# pc_sensything_v1_2.net
KiCad netlist of a schematic drawn in EAGLE
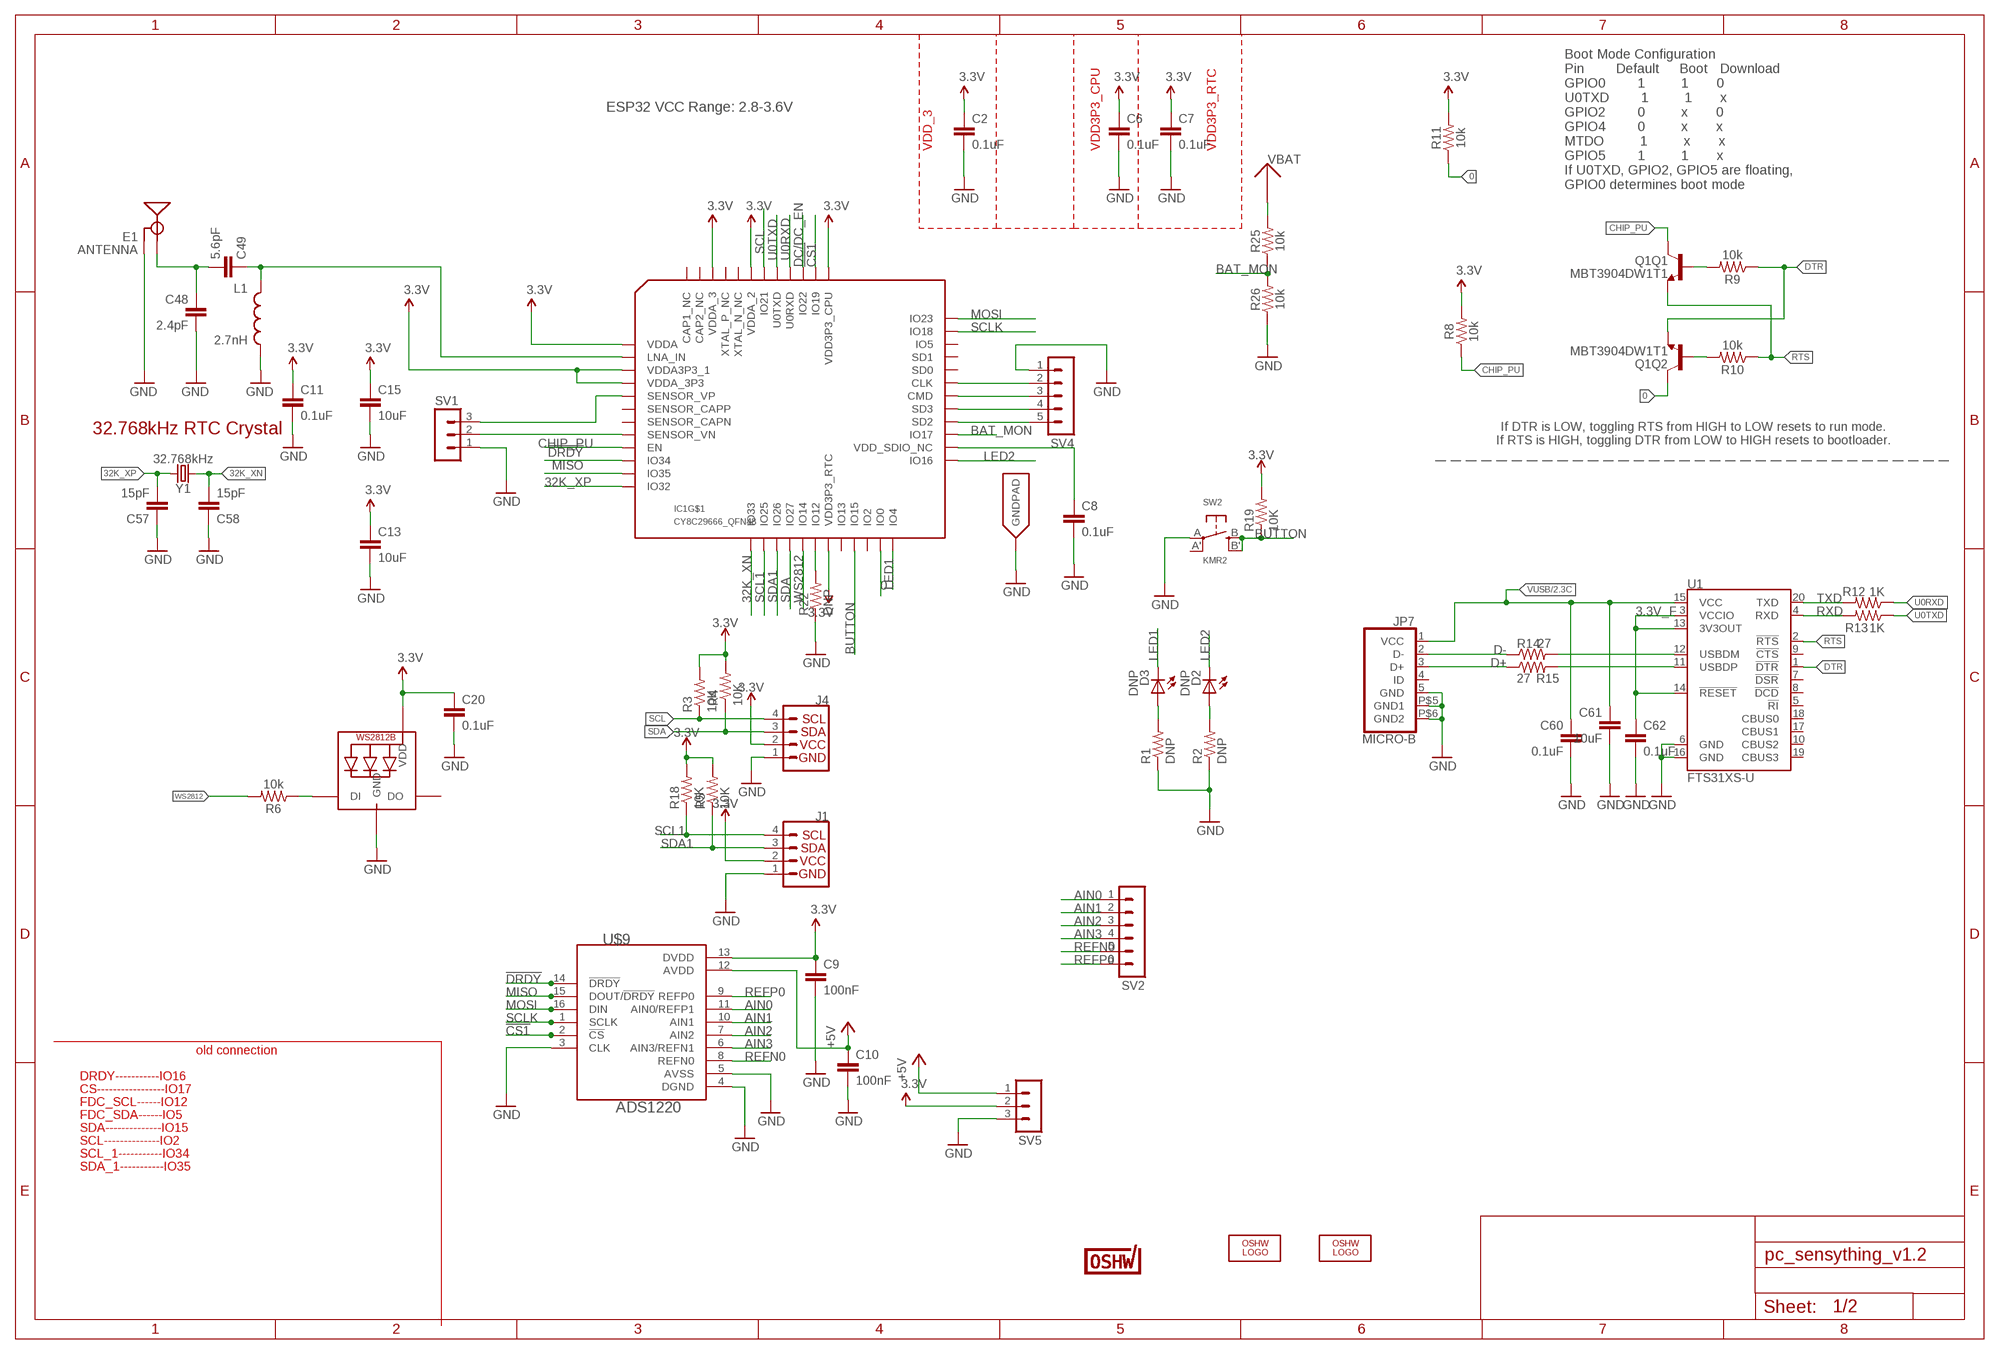
[diagram p0: schematic, sheet 1]
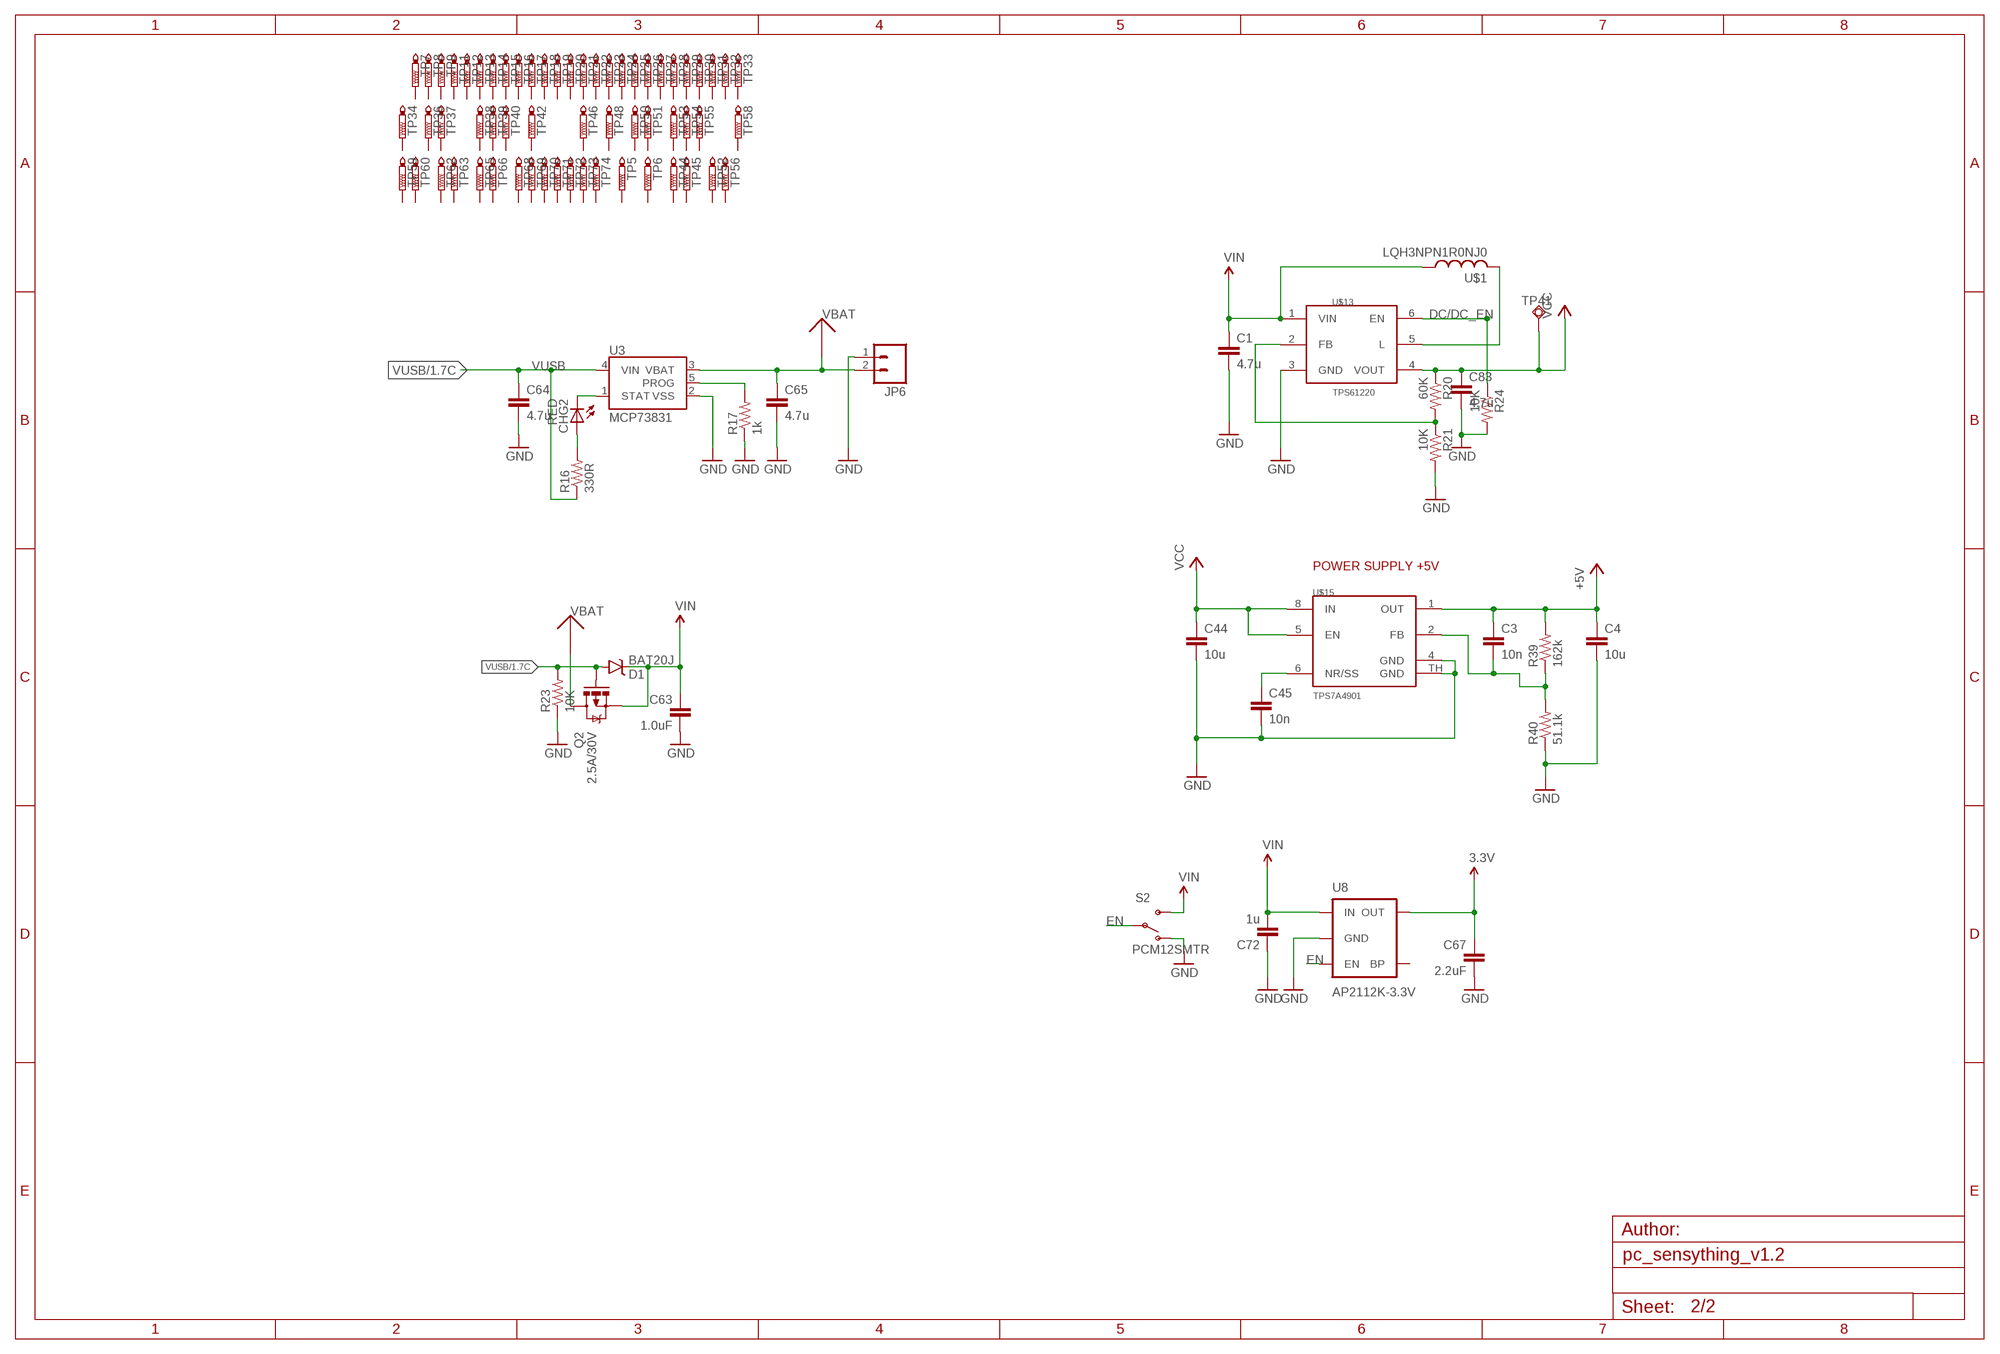
[diagram p1: schematic, sheet 2]

(export (version "E")
  (design (tool "Eeschema 10.0.6"))
  (components
    (comp (ref "C1")
      (value "4.7u")
      (footprint "eagle-import:C0805")
      (libsource (lib "eagle-import") (part "C-EUC0805"))
    )
    (comp (ref "C3")
      (value "10n")
      (footprint "eagle-import:C0402")
      (libsource (lib "eagle-import") (part "C-EUC0402"))
    )
    (comp (ref "C4")
      (value "10u")
      (footprint "eagle-import:C0805")
      (libsource (lib "eagle-import") (part "C-EUC0805"))
    )
    (comp (ref "C44")
      (value "10u")
      (footprint "eagle-import:C0805")
      (libsource (lib "eagle-import") (part "C-EUC0805"))
    )
    (comp (ref "C45")
      (value "10n")
      (footprint "eagle-import:C0402")
      (libsource (lib "eagle-import") (part "C-EUC0402"))
    )
    (comp (ref "C63")
      (value "1.0uF")
      (footprint "eagle-import:C0402")
      (libsource (lib "eagle-import") (part "C-EUC0402"))
    )
    (comp (ref "C64")
      (value "4.7u")
      (footprint "eagle-import:C0805")
      (libsource (lib "eagle-import") (part "C-EUC0805"))
    )
    (comp (ref "C65")
      (value "4.7u")
      (footprint "eagle-import:C0805")
      (libsource (lib "eagle-import") (part "C-EUC0805"))
    )
    (comp (ref "C67")
      (value "2.2uF")
      (footprint "eagle-import:C0402")
      (libsource (lib "eagle-import") (part "C-EUC0402"))
    )
    (comp (ref "C72")
      (value "1u")
      (footprint "eagle-import:C0402")
      (libsource (lib "eagle-import") (part "C-EUC0402"))
    )
    (comp (ref "C83")
      (value "4.7u")
      (footprint "eagle-import:C0805")
      (libsource (lib "eagle-import") (part "C-EUC0805"))
    )
    (comp (ref "CHG2")
      (value "RED")
      (footprint "eagle-import:CHIPLED_0603")
      (libsource (lib "eagle-import") (part "LEDCHIPLED_0603"))
    )
    (comp (ref "D1")
      (value "BAT20J")
      (footprint "eagle-import:SOD-323")
      (libsource (lib "eagle-import") (part "DIODE-SCHOTTKY-BAT20J"))
    )
    (comp (ref "JP6")
      (value "M02-JST-2MM-SMT")
      (footprint "eagle-import:JST-2-SMD")
      (libsource (lib "eagle-import") (part "M02-JST-2MM-SMT"))
    )
    (comp (ref "Q2")
      (value "2.5A/30V")
      (footprint "eagle-import:SOT23-3")
      (libsource (lib "eagle-import") (part "MOSFET-PCHANNELDMG2307L"))
    )
    (comp (ref "R16")
      (value "330R")
      (footprint "eagle-import:R0402")
      (libsource (lib "eagle-import") (part "R-US_R0402"))
    )
    (comp (ref "R17")
      (value "1k")
      (footprint "eagle-import:R0402")
      (libsource (lib "eagle-import") (part "R-US_R0402"))
    )
    (comp (ref "R20")
      (value "60K")
      (footprint "eagle-import:R0805")
      (libsource (lib "eagle-import") (part "R-US_R0805"))
    )
    (comp (ref "R21")
      (value "10K")
      (footprint "eagle-import:R0805")
      (libsource (lib "eagle-import") (part "R-US_R0805"))
    )
    (comp (ref "R23")
      (value "10K")
      (footprint "eagle-import:R0402")
      (libsource (lib "eagle-import") (part "R-US_R0402"))
    )
    (comp (ref "R24")
      (value "10K")
      (footprint "eagle-import:R0402")
      (libsource (lib "eagle-import") (part "R-US_R0402"))
    )
    (comp (ref "R39")
      (value "162k")
      (footprint "eagle-import:R0805")
      (libsource (lib "eagle-import") (part "R-US_R0805"))
    )
    (comp (ref "R40")
      (value "51.1k")
      (footprint "eagle-import:R0805")
      (libsource (lib "eagle-import") (part "R-US_R0805"))
    )
    (comp (ref "S2")
      (value "PCM12SMTR")
      (footprint "eagle-import:SWITCH-SPST-SMD-A")
      (libsource (lib "eagle-import") (part "SWITCH-SPDT-SMD-A"))
    )
    (comp (ref "TP5")
      (value "PTR1PAD1-13")
      (footprint "eagle-import:P1-13")
      (libsource (lib "eagle-import") (part "PTR1PAD1-13"))
    )
    (comp (ref "TP6")
      (value "PTR1PAD1-13")
      (footprint "eagle-import:P1-13")
      (libsource (lib "eagle-import") (part "PTR1PAD1-13"))
    )
    (comp (ref "TP7")
      (value "PTR1PAD1-13")
      (footprint "eagle-import:P1-13")
      (libsource (lib "eagle-import") (part "PTR1PAD1-13"))
    )
    (comp (ref "TP8")
      (value "PTR1PAD1-13")
      (footprint "eagle-import:P1-13")
      (libsource (lib "eagle-import") (part "PTR1PAD1-13"))
    )
    (comp (ref "TP9")
      (value "PTR1PAD1-13")
      (footprint "eagle-import:P1-13")
      (libsource (lib "eagle-import") (part "PTR1PAD1-13"))
    )
    (comp (ref "TP11")
      (value "PTR1PAD1-13")
      (footprint "eagle-import:P1-13")
      (libsource (lib "eagle-import") (part "PTR1PAD1-13"))
    )
    (comp (ref "TP12")
      (value "PTR1PAD1-13")
      (footprint "eagle-import:P1-13")
      (libsource (lib "eagle-import") (part "PTR1PAD1-13"))
    )
    (comp (ref "TP13")
      (value "PTR1PAD1-13")
      (footprint "eagle-import:P1-13")
      (libsource (lib "eagle-import") (part "PTR1PAD1-13"))
    )
    (comp (ref "TP14")
      (value "PTR1PAD1-13")
      (footprint "eagle-import:P1-13")
      (libsource (lib "eagle-import") (part "PTR1PAD1-13"))
    )
    (comp (ref "TP15")
      (value "PTR1PAD1-13")
      (footprint "eagle-import:P1-13")
      (libsource (lib "eagle-import") (part "PTR1PAD1-13"))
    )
    (comp (ref "TP16")
      (value "PTR1PAD1-13")
      (footprint "eagle-import:P1-13")
      (libsource (lib "eagle-import") (part "PTR1PAD1-13"))
    )
    (comp (ref "TP17")
      (value "PTR1PAD1-13")
      (footprint "eagle-import:P1-13")
      (libsource (lib "eagle-import") (part "PTR1PAD1-13"))
    )
    (comp (ref "TP18")
      (value "PTR1PAD1-13")
      (footprint "eagle-import:P1-13")
      (libsource (lib "eagle-import") (part "PTR1PAD1-13"))
    )
    (comp (ref "TP19")
      (value "PTR1PAD1-13")
      (footprint "eagle-import:P1-13")
      (libsource (lib "eagle-import") (part "PTR1PAD1-13"))
    )
    (comp (ref "TP20")
      (value "PTR1PAD1-13")
      (footprint "eagle-import:P1-13")
      (libsource (lib "eagle-import") (part "PTR1PAD1-13"))
    )
    (comp (ref "TP21")
      (value "PTR1PAD1-13")
      (footprint "eagle-import:P1-13")
      (libsource (lib "eagle-import") (part "PTR1PAD1-13"))
    )
    (comp (ref "TP22")
      (value "PTR1PAD1-13")
      (footprint "eagle-import:P1-13")
      (libsource (lib "eagle-import") (part "PTR1PAD1-13"))
    )
    (comp (ref "TP23")
      (value "PTR1PAD1-13")
      (footprint "eagle-import:P1-13")
      (libsource (lib "eagle-import") (part "PTR1PAD1-13"))
    )
    (comp (ref "TP24")
      (value "PTR1PAD1-13")
      (footprint "eagle-import:P1-13")
      (libsource (lib "eagle-import") (part "PTR1PAD1-13"))
    )
    (comp (ref "TP25")
      (value "PTR1PAD1-13")
      (footprint "eagle-import:P1-13")
      (libsource (lib "eagle-import") (part "PTR1PAD1-13"))
    )
    (comp (ref "TP26")
      (value "PTR1PAD1-13")
      (footprint "eagle-import:P1-13")
      (libsource (lib "eagle-import") (part "PTR1PAD1-13"))
    )
    (comp (ref "TP27")
      (value "PTR1PAD1-13")
      (footprint "eagle-import:P1-13")
      (libsource (lib "eagle-import") (part "PTR1PAD1-13"))
    )
    (comp (ref "TP28")
      (value "PTR1PAD1-13")
      (footprint "eagle-import:P1-13")
      (libsource (lib "eagle-import") (part "PTR1PAD1-13"))
    )
    (comp (ref "TP29")
      (value "PTR1PAD1-13")
      (footprint "eagle-import:P1-13")
      (libsource (lib "eagle-import") (part "PTR1PAD1-13"))
    )
    (comp (ref "TP30")
      (value "PTR1PAD1-13")
      (footprint "eagle-import:P1-13")
      (libsource (lib "eagle-import") (part "PTR1PAD1-13"))
    )
    (comp (ref "TP31")
      (value "PTR1PAD1-13")
      (footprint "eagle-import:P1-13")
      (libsource (lib "eagle-import") (part "PTR1PAD1-13"))
    )
    (comp (ref "TP32")
      (value "PTR1PAD1-13")
      (footprint "eagle-import:P1-13")
      (libsource (lib "eagle-import") (part "PTR1PAD1-13"))
    )
    (comp (ref "TP33")
      (value "PTR1PAD1-13")
      (footprint "eagle-import:P1-13")
      (libsource (lib "eagle-import") (part "PTR1PAD1-13"))
    )
    (comp (ref "TP34")
      (value "PTR1PAD1-13")
      (footprint "eagle-import:P1-13")
      (libsource (lib "eagle-import") (part "PTR1PAD1-13"))
    )
    (comp (ref "TP36")
      (value "PTR1PAD1-13")
      (footprint "eagle-import:P1-13")
      (libsource (lib "eagle-import") (part "PTR1PAD1-13"))
    )
    (comp (ref "TP37")
      (value "PTR1PAD1-13")
      (footprint "eagle-import:P1-13")
      (libsource (lib "eagle-import") (part "PTR1PAD1-13"))
    )
    (comp (ref "TP38")
      (value "PTR1PAD1-13")
      (footprint "eagle-import:P1-13")
      (libsource (lib "eagle-import") (part "PTR1PAD1-13"))
    )
    (comp (ref "TP39")
      (value "PTR1PAD1-13")
      (footprint "eagle-import:P1-13")
      (libsource (lib "eagle-import") (part "PTR1PAD1-13"))
    )
    (comp (ref "TP40")
      (value "PTR1PAD1-13")
      (footprint "eagle-import:P1-13")
      (libsource (lib "eagle-import") (part "PTR1PAD1-13"))
    )
    (comp (ref "TP41")
      (value "TPSQB1,27")
      (footprint "eagle-import:B1,27")
      (libsource (lib "eagle-import") (part "TPSQB1,27"))
    )
    (comp (ref "TP42")
      (value "PTR1PAD1-13")
      (footprint "eagle-import:P1-13")
      (libsource (lib "eagle-import") (part "PTR1PAD1-13"))
    )
    (comp (ref "TP44")
      (value "PTR1PAD1-13")
      (footprint "eagle-import:P1-13")
      (libsource (lib "eagle-import") (part "PTR1PAD1-13"))
    )
    (comp (ref "TP45")
      (value "PTR1PAD1-13")
      (footprint "eagle-import:P1-13")
      (libsource (lib "eagle-import") (part "PTR1PAD1-13"))
    )
    (comp (ref "TP46")
      (value "PTR1PAD1-13")
      (footprint "eagle-import:P1-13")
      (libsource (lib "eagle-import") (part "PTR1PAD1-13"))
    )
    (comp (ref "TP48")
      (value "PTR1PAD1-13")
      (footprint "eagle-import:P1-13")
      (libsource (lib "eagle-import") (part "PTR1PAD1-13"))
    )
    (comp (ref "TP50")
      (value "PTR1PAD1-13")
      (footprint "eagle-import:P1-13")
      (libsource (lib "eagle-import") (part "PTR1PAD1-13"))
    )
    (comp (ref "TP51")
      (value "PTR1PAD1-13")
      (footprint "eagle-import:P1-13")
      (libsource (lib "eagle-import") (part "PTR1PAD1-13"))
    )
    (comp (ref "TP52")
      (value "PTR1PAD1-13")
      (footprint "eagle-import:P1-13")
      (libsource (lib "eagle-import") (part "PTR1PAD1-13"))
    )
    (comp (ref "TP53")
      (value "PTR1PAD1-13")
      (footprint "eagle-import:P1-13")
      (libsource (lib "eagle-import") (part "PTR1PAD1-13"))
    )
    (comp (ref "TP54")
      (value "PTR1PAD1-13")
      (footprint "eagle-import:P1-13")
      (libsource (lib "eagle-import") (part "PTR1PAD1-13"))
    )
    (comp (ref "TP55")
      (value "PTR1PAD1-13")
      (footprint "eagle-import:P1-13")
      (libsource (lib "eagle-import") (part "PTR1PAD1-13"))
    )
    (comp (ref "TP56")
      (value "PTR1PAD1-13")
      (footprint "eagle-import:P1-13")
      (libsource (lib "eagle-import") (part "PTR1PAD1-13"))
    )
    (comp (ref "TP58")
      (value "PTR1PAD1-13")
      (footprint "eagle-import:P1-13")
      (libsource (lib "eagle-import") (part "PTR1PAD1-13"))
    )
    (comp (ref "TP59")
      (value "PTR1PAD1-13")
      (footprint "eagle-import:P1-13")
      (libsource (lib "eagle-import") (part "PTR1PAD1-13"))
    )
    (comp (ref "TP60")
      (value "PTR1PAD1-13")
      (footprint "eagle-import:P1-13")
      (libsource (lib "eagle-import") (part "PTR1PAD1-13"))
    )
    (comp (ref "TP62")
      (value "PTR1PAD1-13")
      (footprint "eagle-import:P1-13")
      (libsource (lib "eagle-import") (part "PTR1PAD1-13"))
    )
    (comp (ref "TP63")
      (value "PTR1PAD1-13")
      (footprint "eagle-import:P1-13")
      (libsource (lib "eagle-import") (part "PTR1PAD1-13"))
    )
    (comp (ref "TP65")
      (value "PTR1PAD1-13")
      (footprint "eagle-import:P1-13")
      (libsource (lib "eagle-import") (part "PTR1PAD1-13"))
    )
    (comp (ref "TP66")
      (value "PTR1PAD1-13")
      (footprint "eagle-import:P1-13")
      (libsource (lib "eagle-import") (part "PTR1PAD1-13"))
    )
    (comp (ref "TP68")
      (value "PTR1PAD1-13")
      (footprint "eagle-import:P1-13")
      (libsource (lib "eagle-import") (part "PTR1PAD1-13"))
    )
    (comp (ref "TP69")
      (value "PTR1PAD1-13")
      (footprint "eagle-import:P1-13")
      (libsource (lib "eagle-import") (part "PTR1PAD1-13"))
    )
    (comp (ref "TP70")
      (value "PTR1PAD1-13")
      (footprint "eagle-import:P1-13")
      (libsource (lib "eagle-import") (part "PTR1PAD1-13"))
    )
    (comp (ref "TP71")
      (value "PTR1PAD1-13")
      (footprint "eagle-import:P1-13")
      (libsource (lib "eagle-import") (part "PTR1PAD1-13"))
    )
    (comp (ref "TP72")
      (value "PTR1PAD1-13")
      (footprint "eagle-import:P1-13")
      (libsource (lib "eagle-import") (part "PTR1PAD1-13"))
    )
    (comp (ref "TP73")
      (value "PTR1PAD1-13")
      (footprint "eagle-import:P1-13")
      (libsource (lib "eagle-import") (part "PTR1PAD1-13"))
    )
    (comp (ref "TP74")
      (value "PTR1PAD1-13")
      (footprint "eagle-import:P1-13")
      (libsource (lib "eagle-import") (part "PTR1PAD1-13"))
    )
    (comp (ref "U$1")
      (value "LQH3NPN1R0NJ0")
      (footprint "eagle-import:LQH3NP")
      (libsource (lib "eagle-import") (part "LQH3NPN1R0NJ0"))
    )
    (comp (ref "U$13")
      (value "TPS61220")
      (footprint "eagle-import:SC-70-6")
      (libsource (lib "eagle-import") (part "TPS61222"))
    )
    (comp (ref "U$15")
      (value "TPS7A4901")
      (footprint "eagle-import:S-PDSO-G08")
      (libsource (lib "eagle-import") (part "TPS7A4901"))
    )
    (comp (ref "U3")
      (value "MCP73831")
      (footprint "eagle-import:SOT23-5")
      (libsource (lib "eagle-import") (part "MCP73831"))
    )
    (comp (ref "U8")
      (value "AP2112K-3.3V")
      (footprint "eagle-import:SOT23-5")
      (libsource (lib "eagle-import") (part "V_REG_LDOSMD"))
    )
    (comp (ref "C2")
      (value "0.1uF")
      (footprint "eagle-import:0402")
      (libsource (lib "eagle-import") (part "0.1UF-0402-16V-10%"))
    )
    (comp (ref "C6")
      (value "0.1uF")
      (footprint "eagle-import:0402")
      (libsource (lib "eagle-import") (part "0.1UF-0402-16V-10%"))
    )
    (comp (ref "C7")
      (value "0.1uF")
      (footprint "eagle-import:0402")
      (libsource (lib "eagle-import") (part "0.1UF-0402-16V-10%"))
    )
    (comp (ref "C8")
      (value "0.1uF")
      (footprint "eagle-import:0402")
      (libsource (lib "eagle-import") (part "0.1UF-0402-16V-10%"))
    )
    (comp (ref "C9")
      (value "100nF")
      (footprint "eagle-import:C0805")
      (libsource (lib "eagle-import") (part "C-EUC0805"))
    )
    (comp (ref "C10")
      (value "100nF")
      (footprint "eagle-import:C0805")
      (libsource (lib "eagle-import") (part "C-EUC0805"))
    )
    (comp (ref "C11")
      (value "0.1uF")
      (footprint "eagle-import:0402")
      (libsource (lib "eagle-import") (part "0.1UF-0402-16V-10%"))
    )
    (comp (ref "C13")
      (value "10uF")
      (footprint "eagle-import:0603")
      (libsource (lib "eagle-import") (part "10UF-0603-6.3V-20%"))
    )
    (comp (ref "C15")
      (value "10uF")
      (footprint "eagle-import:0603")
      (libsource (lib "eagle-import") (part "10UF-0603-6.3V-20%"))
    )
    (comp (ref "C20")
      (value "0.1uF")
      (footprint "eagle-import:0603")
      (libsource (lib "eagle-import") (part "0.1UF-0603-25V-(+80/-20%)"))
    )
    (comp (ref "C48")
      (value "2.4pF")
      (footprint "eagle-import:0603")
      (libsource (lib "eagle-import") (part "2.4PF-0603-50V-5%"))
    )
    (comp (ref "C49")
      (value "5.6pF")
      (footprint "eagle-import:0603")
      (libsource (lib "eagle-import") (part "5.6PF-50V-5%(0603)"))
    )
    (comp (ref "C57")
      (value "15pF")
      (footprint "eagle-import:0603")
      (libsource (lib "eagle-import") (part "15PF-0603-50V-5%"))
    )
    (comp (ref "C58")
      (value "15pF")
      (footprint "eagle-import:0603")
      (libsource (lib "eagle-import") (part "15PF-0603-50V-5%"))
    )
    (comp (ref "C60")
      (value "0.1uF")
      (footprint "eagle-import:C0402")
      (libsource (lib "eagle-import") (part "C-EUC0402"))
    )
    (comp (ref "C61")
      (value "10uF")
      (footprint "eagle-import:C0805")
      (libsource (lib "eagle-import") (part "C-EUC0805"))
    )
    (comp (ref "C62")
      (value "0.1uF")
      (footprint "eagle-import:C0402")
      (libsource (lib "eagle-import") (part "C-EUC0402"))
    )
    (comp (ref "D2")
      (value "DNP")
      (footprint "eagle-import:CHIPLED_0603")
      (libsource (lib "eagle-import") (part "LEDCHIPLED_0603"))
    )
    (comp (ref "D3")
      (value "DNP")
      (footprint "eagle-import:CHIPLED_0603")
      (libsource (lib "eagle-import") (part "LEDCHIPLED_0603"))
    )
    (comp (ref "E1")
      (value "ANTENNA")
      (footprint "eagle-import:TRACE_ANTENNA_2.4GHZ_25.7MM_TUNED")
      (libsource (lib "eagle-import") (part "ANTENNATRACE-TUNED"))
    )
    (comp (ref "IC1")
      (value "CY8C29666_QFN48")
      (footprint "eagle-import:QFN48")
      (libsource (lib "eagle-import") (part "CY8C29666_QFN48"))
    )
    (comp (ref "J1")
      (value "QWIIC_CONNECTORJS-1MM")
      (footprint "eagle-import:1X04_1MM_RA")
      (libsource (lib "eagle-import") (part "QWIIC_CONNECTORJS-1MM"))
    )
    (comp (ref "J4")
      (value "QWIIC_CONNECTORJS-1MM")
      (footprint "eagle-import:1X04_1MM_RA")
      (libsource (lib "eagle-import") (part "QWIIC_CONNECTORJS-1MM"))
    )
    (comp (ref "JP7")
      (value "MICRO-B")
      (footprint "eagle-import:MICRO-B")
      (libsource (lib "eagle-import") (part "MICRO-B"))
    )
    (comp (ref "L1")
      (value "2.7nH")
      (footprint "eagle-import:0603")
      (libsource (lib "eagle-import") (part "INDUCTOR0603"))
    )
    (comp (ref "LED1")
      (value "WS2812B5050")
      (footprint "eagle-import:WS2812B")
      (libsource (lib "eagle-import") (part "WS2812B5050"))
    )
    (comp (ref "LOGO1")
      (value "OSHW_LOGO_FILLX0200-NT")
      (footprint "eagle-import:OSHW_FILLX200_NOTEXT")
      (libsource (lib "eagle-import") (part "OSHW_LOGO_FILLX0200-NT"))
    )
    (comp (ref "LOGO3")
      (value "OSHW_LOGO_FILLX0200-NT")
      (footprint "eagle-import:OSHW_FILLX200_NOTEXT")
      (libsource (lib "eagle-import") (part "OSHW_LOGO_FILLX0200-NT"))
    )
    (comp (ref "Q1")
      (value "MBT3904DW1T1")
      (footprint "eagle-import:SC70-6")
      (libsource (lib "eagle-import") (part "MBT3904DW1T1"))
    )
    (comp (ref "R1")
      (value "DNP")
      (footprint "eagle-import:R0402")
      (libsource (lib "eagle-import") (part "R-US_R0402"))
    )
    (comp (ref "R2")
      (value "DNP")
      (footprint "eagle-import:R0402")
      (libsource (lib "eagle-import") (part "R-US_R0402"))
    )
    (comp (ref "R3")
      (value "10K")
      (footprint "eagle-import:R0402")
      (libsource (lib "eagle-import") (part "R-US_R0402"))
    )
    (comp (ref "R4")
      (value "10K")
      (footprint "eagle-import:R0402")
      (libsource (lib "eagle-import") (part "R-US_R0402"))
    )
    (comp (ref "R5")
      (value "10K")
      (footprint "eagle-import:R0402")
      (libsource (lib "eagle-import") (part "R-US_R0402"))
    )
    (comp (ref "R6")
      (value "10k")
      (footprint "eagle-import:0603")
      (libsource (lib "eagle-import") (part "10KOHM-1/10W-1%(0603)0603"))
    )
    (comp (ref "R8")
      (value "10k")
      (footprint "eagle-import:0603")
      (libsource (lib "eagle-import") (part "10KOHM-1/10W-1%(0603)0603"))
    )
    (comp (ref "R9")
      (value "10k")
      (footprint "eagle-import:0603")
      (libsource (lib "eagle-import") (part "10KOHM-0603-1/10W-1%"))
    )
    (comp (ref "R10")
      (value "10k")
      (footprint "eagle-import:0603")
      (libsource (lib "eagle-import") (part "10KOHM-0603-1/10W-1%"))
    )
    (comp (ref "R11")
      (value "10k")
      (footprint "eagle-import:0603")
      (libsource (lib "eagle-import") (part "10KOHM-1/10W-1%(0603)0603"))
    )
    (comp (ref "R12")
      (value "1K")
      (footprint "eagle-import:R0402")
      (libsource (lib "eagle-import") (part "R-US_R0402"))
    )
    (comp (ref "R13")
      (value "1K")
      (footprint "eagle-import:R0402")
      (libsource (lib "eagle-import") (part "R-US_R0402"))
    )
    (comp (ref "R14")
      (value "27")
      (footprint "eagle-import:R0402")
      (libsource (lib "eagle-import") (part "R-US_R0402"))
    )
    (comp (ref "R15")
      (value "27")
      (footprint "eagle-import:R0402")
      (libsource (lib "eagle-import") (part "R-US_R0402"))
    )
    (comp (ref "R18")
      (value "10K")
      (footprint "eagle-import:R0402")
      (libsource (lib "eagle-import") (part "R-US_R0402"))
    )
    (comp (ref "R19")
      (value "10K")
      (footprint "eagle-import:R0402")
      (libsource (lib "eagle-import") (part "R-US_R0402"))
    )
    (comp (ref "R22")
      (value "DNP")
      (footprint "eagle-import:R0402")
      (libsource (lib "eagle-import") (part "R-US_R0402"))
    )
    (comp (ref "R25")
      (value "10k")
      (footprint "eagle-import:0603")
      (libsource (lib "eagle-import") (part "10KOHM-1/10W-1%(0603)0603"))
    )
    (comp (ref "R26")
      (value "10k")
      (footprint "eagle-import:0603")
      (libsource (lib "eagle-import") (part "10KOHM-1/10W-1%(0603)0603"))
    )
    (comp (ref "SV1")
      (value "MA03-1")
      (footprint "eagle-import:MA03-1")
      (libsource (lib "eagle-import") (part "MA03-1"))
    )
    (comp (ref "SV2")
      (value "MA06-1")
      (footprint "eagle-import:MA06-1")
      (libsource (lib "eagle-import") (part "MA06-1"))
    )
    (comp (ref "SV4")
      (value "MA05-1")
      (footprint "eagle-import:MA05-1")
      (libsource (lib "eagle-import") (part "MA05-1"))
    )
    (comp (ref "SV5")
      (value "MA03-1")
      (footprint "eagle-import:MA03-1")
      (libsource (lib "eagle-import") (part "MA03-1"))
    )
    (comp (ref "SW2")
      (value "KMR2")
      (footprint "eagle-import:BTN_KMR2_4.6X2.8")
      (libsource (lib "eagle-import") (part "SWITCH_TACT_SMT4.6X2.8"))
    )
    (comp (ref "U$9")
      (value "ADS1220")
      (footprint "eagle-import:TSSOP-16")
      (libsource (lib "eagle-import") (part "ADS1220"))
    )
    (comp (ref "U$22")
      (value "CERT-SMALL")
      (footprint "eagle-import:CERT-SMALL-SILK")
      (libsource (lib "eagle-import") (part "CERT-SMALL"))
    )
    (comp (ref "U1")
      (value "FTS31XS-U")
      (footprint "eagle-import:SSOP20_L")
      (libsource (lib "eagle-import") (part "FT231XS"))
    )
    (comp (ref "Y1")
      (value "32.768kHz")
      (footprint "eagle-import:CRYSTAL-SMD-3.2X1.5MM")
      (libsource (lib "eagle-import") (part "CRYSTAL-32.768KHZSMD-3.2X1.5"))
    )
  )
  (nets
    (net (code "1") (name "+5V") (class "Default")
      (node (ref "C10") (pin "1") (pinfunction "1_1") (pintype "passive"))
      (node (ref "C3") (pin "1") (pinfunction "1_1") (pintype "passive"))
      (node (ref "C4") (pin "1") (pinfunction "1_1") (pintype "passive"))
      (node (ref "R39") (pin "2") (pinfunction "2_2") (pintype "passive"))
      (node (ref "SV5") (pin "1") (pinfunction "1_1") (pintype "passive"))
      (node (ref "U$15") (pin "1") (pinfunction "OUT_1") (pintype "bidirectional"))
      (node (ref "U$9") (pin "12") (pinfunction "AVDD_12") (pintype "bidirectional"))
    )
    (net (code "2") (name "0") (class "Default")
      (node (ref "IC1") (pin "23") (pinfunction "IO0_23") (pintype "bidirectional"))
      (node (ref "Q1") (pin "6") (pinfunction "C_6") (pintype "passive"))
      (node (ref "R11") (pin "1") (pinfunction "1_1") (pintype "passive"))
    )
    (net (code "3") (name "3.3V") (class "Default")
      (node (ref "C11") (pin "1") (pinfunction "1_1") (pintype "passive"))
      (node (ref "C13") (pin "1") (pinfunction "1_1") (pintype "passive"))
      (node (ref "C15") (pin "1") (pinfunction "1_1") (pintype "passive"))
      (node (ref "C2") (pin "1") (pinfunction "1_1") (pintype "passive"))
      (node (ref "C20") (pin "1") (pinfunction "1_1") (pintype "passive"))
      (node (ref "C6") (pin "1") (pinfunction "1_1") (pintype "passive"))
      (node (ref "C67") (pin "1") (pinfunction "1_1") (pintype "passive"))
      (node (ref "C7") (pin "1") (pinfunction "1_1") (pintype "passive"))
      (node (ref "C9") (pin "1") (pinfunction "1_1") (pintype "passive"))
      (node (ref "IC1") (pin "1") (pinfunction "VDDA_1") (pintype "bidirectional"))
      (node (ref "IC1") (pin "19") (pinfunction "VDD3P3_RTC_19") (pintype "bidirectional"))
      (node (ref "IC1") (pin "3") (pinfunction "VDDA3P3_1_3") (pintype "bidirectional"))
      (node (ref "IC1") (pin "37") (pinfunction "VDD3P3_CPU_37") (pintype "bidirectional"))
      (node (ref "IC1") (pin "4") (pinfunction "VDDA_3P3_4") (pintype "bidirectional"))
      (node (ref "IC1") (pin "43") (pinfunction "VDDA_2_43") (pintype "bidirectional"))
      (node (ref "IC1") (pin "46") (pinfunction "VDDA_3_46") (pintype "bidirectional"))
      (node (ref "J1") (pin "2") (pinfunction "2_2") (pintype "power_in"))
      (node (ref "J4") (pin "2") (pinfunction "2_2") (pintype "power_in"))
      (node (ref "LED1") (pin "1-VDD") (pinfunction "VDD_1-VDD") (pintype "power_in"))
      (node (ref "R11") (pin "2") (pinfunction "2_2") (pintype "passive"))
      (node (ref "R18") (pin "2") (pinfunction "2_2") (pintype "passive"))
      (node (ref "R19") (pin "2") (pinfunction "2_2") (pintype "passive"))
      (node (ref "R3") (pin "2") (pinfunction "2_2") (pintype "passive"))
      (node (ref "R4") (pin "2") (pinfunction "2_2") (pintype "passive"))
      (node (ref "R5") (pin "2") (pinfunction "2_2") (pintype "passive"))
      (node (ref "R8") (pin "2") (pinfunction "2_2") (pintype "passive"))
      (node (ref "SV5") (pin "2") (pinfunction "2_2") (pintype "passive"))
      (node (ref "U$9") (pin "13") (pinfunction "DVDD_13") (pintype "bidirectional"))
      (node (ref "U8") (pin "5") (pinfunction "OUT_5") (pintype "passive"))
    )
    (net (code "4") (name "3.3V_F") (class "Default")
      (node (ref "C62") (pin "1") (pinfunction "1_1") (pintype "passive"))
      (node (ref "U1") (pin "13") (pinfunction "3V3OUT_13") (pintype "bidirectional"))
      (node (ref "U1") (pin "14") (pinfunction "~{RESET}_14") (pintype "bidirectional"))
      (node (ref "U1") (pin "3") (pinfunction "VCCIO_3") (pintype "bidirectional"))
    )
    (net (code "5") (name "32K_XN") (class "Default")
      (node (ref "C58") (pin "2") (pinfunction "2_2") (pintype "passive"))
      (node (ref "IC1") (pin "13") (pinfunction "IO33_13") (pintype "bidirectional"))
      (node (ref "Y1") (pin "P$2") (pinfunction "2_P$2") (pintype "passive"))
    )
    (net (code "6") (name "32K_XP") (class "Default")
      (node (ref "C57") (pin "2") (pinfunction "2_2") (pintype "passive"))
      (node (ref "IC1") (pin "12") (pinfunction "IO32_12") (pintype "bidirectional"))
      (node (ref "Y1") (pin "P$1") (pinfunction "1_P$1") (pintype "passive"))
    )
    (net (code "7") (name "AIN0") (class "Default")
      (node (ref "SV2") (pin "1") (pinfunction "1_1") (pintype "passive"))
      (node (ref "U$9") (pin "11") (pinfunction "AIN0/REFP1_11") (pintype "bidirectional"))
    )
    (net (code "8") (name "AIN1") (class "Default")
      (node (ref "SV2") (pin "2") (pinfunction "2_2") (pintype "passive"))
      (node (ref "U$9") (pin "10") (pinfunction "AIN1_10") (pintype "bidirectional"))
    )
    (net (code "9") (name "AIN2") (class "Default")
      (node (ref "SV2") (pin "3") (pinfunction "3_3") (pintype "passive"))
      (node (ref "U$9") (pin "7") (pinfunction "AIN2_7") (pintype "bidirectional"))
    )
    (net (code "10") (name "AIN3") (class "Default")
      (node (ref "SV2") (pin "4") (pinfunction "4_4") (pintype "passive"))
      (node (ref "U$9") (pin "6") (pinfunction "AIN3/REFN1_6") (pintype "bidirectional"))
    )
    (net (code "11") (name "BAT_MON") (class "Default")
      (node (ref "IC1") (pin "27") (pinfunction "IO17_27") (pintype "bidirectional"))
      (node (ref "R25") (pin "1") (pinfunction "1_1") (pintype "passive"))
      (node (ref "R26") (pin "2") (pinfunction "2_2") (pintype "passive"))
    )
    (net (code "12") (name "BUTTON") (class "Default")
      (node (ref "IC1") (pin "21") (pinfunction "IO15_21") (pintype "bidirectional"))
      (node (ref "R19") (pin "1") (pinfunction "1_1") (pintype "passive"))
      (node (ref "SW2") (pin "B") (pinfunction "S_B") (pintype "passive"))
      (node (ref "SW2") (pin "B'") (pinfunction "S1_B'") (pintype "passive"))
    )
    (net (code "13") (name "CHIP_PU") (class "Default")
      (node (ref "IC1") (pin "9") (pinfunction "EN_9") (pintype "bidirectional"))
      (node (ref "Q1") (pin "3") (pinfunction "C_3") (pintype "passive"))
      (node (ref "R8") (pin "1") (pinfunction "1_1") (pintype "passive"))
    )
    (net (code "14") (name "D+") (class "Default")
      (node (ref "JP7") (pin "3") (pinfunction "D+_3") (pintype "bidirectional"))
      (node (ref "R15") (pin "1") (pinfunction "1_1") (pintype "passive"))
    )
    (net (code "15") (name "D-") (class "Default")
      (node (ref "JP7") (pin "2") (pinfunction "D-_2") (pintype "bidirectional"))
      (node (ref "R14") (pin "1") (pinfunction "1_1") (pintype "passive"))
    )
    (net (code "16") (name "DC{slash}DC_EN") (class "Default")
      (node (ref "IC1") (pin "39") (pinfunction "IO22_39") (pintype "bidirectional"))
      (node (ref "R24") (pin "1") (pinfunction "1_1") (pintype "passive"))
      (node (ref "U$13") (pin "6") (pinfunction "EN_6") (pintype "bidirectional"))
    )
    (net (code "17") (name "DTR") (class "Default")
      (node (ref "Q1") (pin "1") (pinfunction "E_1") (pintype "passive"))
      (node (ref "R9") (pin "1") (pinfunction "1_1") (pintype "passive"))
      (node (ref "U1") (pin "1") (pinfunction "~{DTR}_1") (pintype "bidirectional"))
    )
    (net (code "18") (name "EN") (class "Default")
      (node (ref "S2") (pin "2") (pinfunction "P_2") (pintype "passive"))
      (node (ref "U8") (pin "3") (pinfunction "EN_3") (pintype "input"))
    )
    (net (code "19") (name "GND") (class "Default")
      (node (ref "C1") (pin "2") (pinfunction "2_2") (pintype "passive"))
      (node (ref "C10") (pin "2") (pinfunction "2_2") (pintype "passive"))
      (node (ref "C11") (pin "2") (pinfunction "2_2") (pintype "passive"))
      (node (ref "C13") (pin "2") (pinfunction "2_2") (pintype "passive"))
      (node (ref "C15") (pin "2") (pinfunction "2_2") (pintype "passive"))
      (node (ref "C2") (pin "2") (pinfunction "2_2") (pintype "passive"))
      (node (ref "C20") (pin "2") (pinfunction "2_2") (pintype "passive"))
      (node (ref "C4") (pin "2") (pinfunction "2_2") (pintype "passive"))
      (node (ref "C44") (pin "2") (pinfunction "2_2") (pintype "passive"))
      (node (ref "C45") (pin "2") (pinfunction "2_2") (pintype "passive"))
      (node (ref "C48") (pin "2") (pinfunction "2_2") (pintype "passive"))
      (node (ref "C57") (pin "1") (pinfunction "1_1") (pintype "passive"))
      (node (ref "C58") (pin "1") (pinfunction "1_1") (pintype "passive"))
      (node (ref "C6") (pin "2") (pinfunction "2_2") (pintype "passive"))
      (node (ref "C60") (pin "2") (pinfunction "2_2") (pintype "passive"))
      (node (ref "C61") (pin "2") (pinfunction "2_2") (pintype "passive"))
      (node (ref "C62") (pin "2") (pinfunction "2_2") (pintype "passive"))
      (node (ref "C63") (pin "2") (pinfunction "2_2") (pintype "passive"))
      (node (ref "C64") (pin "2") (pinfunction "2_2") (pintype "passive"))
      (node (ref "C65") (pin "2") (pinfunction "2_2") (pintype "passive"))
      (node (ref "C67") (pin "2") (pinfunction "2_2") (pintype "passive"))
      (node (ref "C7") (pin "2") (pinfunction "2_2") (pintype "passive"))
      (node (ref "C72") (pin "1") (pinfunction "1_1") (pintype "passive"))
      (node (ref "C8") (pin "2") (pinfunction "2_2") (pintype "passive"))
      (node (ref "C83") (pin "2") (pinfunction "2_2") (pintype "passive"))
      (node (ref "C9") (pin "2") (pinfunction "2_2") (pintype "passive"))
      (node (ref "E1") (pin "GND") (pinfunction "GND_GND") (pintype "bidirectional"))
      (node (ref "E1") (pin "GND2") (pinfunction "GND_GND2") (pintype "bidirectional"))
      (node (ref "IC1") (pin "EXP") (pinfunction "GNDPAD_EXP") (pintype "power_in"))
      (node (ref "J1") (pin "1") (pinfunction "1_1") (pintype "power_in"))
      (node (ref "J4") (pin "1") (pinfunction "1_1") (pintype "power_in"))
      (node (ref "JP6") (pin "1") (pinfunction "1_1") (pintype "passive"))
      (node (ref "JP7") (pin "5") (pinfunction "GND_5") (pintype "bidirectional"))
      (node (ref "JP7") (pin "P$5") (pinfunction "GND1_P$5") (pintype "bidirectional"))
      (node (ref "JP7") (pin "P$6") (pinfunction "GND2_P$6") (pintype "bidirectional"))
      (node (ref "L1") (pin "2") (pinfunction "2_2") (pintype "passive"))
      (node (ref "LED1") (pin "3-GND") (pinfunction "GND_3-GND") (pintype "power_in"))
      (node (ref "R1") (pin "1") (pinfunction "1_1") (pintype "passive"))
      (node (ref "R17") (pin "1") (pinfunction "1_1") (pintype "passive"))
      (node (ref "R2") (pin "1") (pinfunction "1_1") (pintype "passive"))
      (node (ref "R21") (pin "2") (pinfunction "2_2") (pintype "passive"))
      (node (ref "R22") (pin "1") (pinfunction "1_1") (pintype "passive"))
      (node (ref "R23") (pin "1") (pinfunction "1_1") (pintype "passive"))
      (node (ref "R24") (pin "2") (pinfunction "2_2") (pintype "passive"))
      (node (ref "R26") (pin "1") (pinfunction "1_1") (pintype "passive"))
      (node (ref "R40") (pin "1") (pinfunction "1_1") (pintype "passive"))
      (node (ref "S2") (pin "1") (pinfunction "O_1") (pintype "passive"))
      (node (ref "SV1") (pin "1") (pinfunction "1_1") (pintype "passive"))
      (node (ref "SV4") (pin "1") (pinfunction "1_1") (pintype "passive"))
      (node (ref "SV5") (pin "3") (pinfunction "3_3") (pintype "passive"))
      (node (ref "SW2") (pin "A") (pinfunction "P_A") (pintype "passive"))
      (node (ref "U$13") (pin "3") (pinfunction "GND_3") (pintype "bidirectional"))
      (node (ref "U$15") (pin "4") (pinfunction "GND_4") (pintype "bidirectional"))
      (node (ref "U$15") (pin "TH") (pinfunction "GND_TH") (pintype "bidirectional"))
      (node (ref "U$9") (pin "3") (pinfunction "CLK_3") (pintype "bidirectional"))
      (node (ref "U$9") (pin "4") (pinfunction "DGND_4") (pintype "bidirectional"))
      (node (ref "U$9") (pin "5") (pinfunction "AVSS_5") (pintype "bidirectional"))
      (node (ref "U1") (pin "16") (pinfunction "GND_16") (pintype "bidirectional"))
      (node (ref "U1") (pin "6") (pinfunction "GND_6") (pintype "bidirectional"))
      (node (ref "U3") (pin "2") (pinfunction "VSS_2") (pintype "power_in"))
      (node (ref "U8") (pin "2") (pinfunction "GND_2") (pintype "input"))
    )
    (net (code "20") (name "LED1") (class "Default")
      (node (ref "D3") (pin "C") (pinfunction "C_C") (pintype "passive"))
      (node (ref "IC1") (pin "24") (pinfunction "IO4_24") (pintype "bidirectional"))
    )
    (net (code "21") (name "LED2") (class "Default")
      (node (ref "D2") (pin "C") (pinfunction "C_C") (pintype "passive"))
      (node (ref "IC1") (pin "25") (pinfunction "IO16_25") (pintype "bidirectional"))
    )
    (net (code "22") (name "MISO") (class "Default")
      (node (ref "IC1") (pin "11") (pinfunction "IO35_11") (pintype "bidirectional"))
      (node (ref "U$9") (pin "15") (pinfunction "DOUT/~{DRDY}_15") (pintype "bidirectional"))
    )
    (net (code "23") (name "MOSI") (class "Default")
      (node (ref "IC1") (pin "36") (pinfunction "IO23_36") (pintype "bidirectional"))
      (node (ref "U$9") (pin "16") (pinfunction "DIN_16") (pintype "bidirectional"))
    )
    (net (code "24") (name "Net-(CHG2-PadA)") (class "Default")
      (node (ref "CHG2") (pin "A") (pinfunction "A_A") (pintype "passive"))
      (node (ref "R16") (pin "2") (pinfunction "2_2") (pintype "passive"))
    )
    (net (code "25") (name "Net-(D2-PadA)") (class "Default")
      (node (ref "D2") (pin "A") (pinfunction "A_A") (pintype "passive"))
      (node (ref "R2") (pin "2") (pinfunction "2_2") (pintype "passive"))
    )
    (net (code "26") (name "Net-(D3-PadA)") (class "Default")
      (node (ref "D3") (pin "A") (pinfunction "A_A") (pintype "passive"))
      (node (ref "R1") (pin "2") (pinfunction "2_2") (pintype "passive"))
    )
    (net (code "27") (name "Net-(E1-SIGNAL)") (class "Default")
      (node (ref "C48") (pin "1") (pinfunction "1_1") (pintype "passive"))
      (node (ref "C49") (pin "2") (pinfunction "2_2") (pintype "passive"))
      (node (ref "E1") (pin "ANT") (pinfunction "SIGNAL_ANT") (pintype "bidirectional"))
    )
    (net (code "28") (name "Net-(IC1A-CLK)") (class "Default")
      (node (ref "IC1") (pin "31") (pinfunction "CLK_31") (pintype "bidirectional"))
      (node (ref "SV4") (pin "2") (pinfunction "2_2") (pintype "passive"))
    )
    (net (code "29") (name "Net-(IC1A-CMD)") (class "Default")
      (node (ref "IC1") (pin "30") (pinfunction "CMD_30") (pintype "bidirectional"))
      (node (ref "SV4") (pin "3") (pinfunction "3_3") (pintype "passive"))
    )
    (net (code "30") (name "Net-(IC1A-IO12)") (class "Default")
      (node (ref "IC1") (pin "18") (pinfunction "IO12_18") (pintype "power_in"))
      (node (ref "R22") (pin "2") (pinfunction "2_2") (pintype "passive"))
    )
    (net (code "31") (name "Net-(IC1A-LNA_IN)") (class "Default")
      (node (ref "C49") (pin "1") (pinfunction "1_1") (pintype "passive"))
      (node (ref "IC1") (pin "2") (pinfunction "LNA_IN_2") (pintype "bidirectional"))
      (node (ref "L1") (pin "1") (pinfunction "1_1") (pintype "passive"))
    )
    (net (code "32") (name "Net-(IC1A-SD2)") (class "Default")
      (node (ref "IC1") (pin "28") (pinfunction "SD2_28") (pintype "bidirectional"))
      (node (ref "SV4") (pin "5") (pinfunction "5_5") (pintype "passive"))
    )
    (net (code "33") (name "Net-(IC1A-SD3)") (class "Default")
      (node (ref "IC1") (pin "29") (pinfunction "SD3_29") (pintype "bidirectional"))
      (node (ref "SV4") (pin "4") (pinfunction "4_4") (pintype "passive"))
    )
    (net (code "34") (name "Net-(IC1A-SENSOR_VN)") (class "Default")
      (node (ref "IC1") (pin "8") (pinfunction "SENSOR_VN_8") (pintype "bidirectional"))
      (node (ref "SV1") (pin "2") (pinfunction "2_2") (pintype "passive"))
    )
    (net (code "35") (name "Net-(IC1A-SENSOR_VP)") (class "Default")
      (node (ref "IC1") (pin "5") (pinfunction "SENSOR_VP_5") (pintype "bidirectional"))
      (node (ref "SV1") (pin "3") (pinfunction "3_3") (pintype "passive"))
    )
    (net (code "36") (name "Net-(IC1A-VDD_SDIO_NC)") (class "Default")
      (node (ref "C8") (pin "1") (pinfunction "1_1") (pintype "passive"))
      (node (ref "IC1") (pin "26") (pinfunction "VDD_SDIO_NC_26") (pintype "bidirectional"))
    )
    (net (code "37") (name "Net-(LED1-DI)") (class "Default")
      (node (ref "LED1") (pin "4-DIN") (pinfunction "DI_4-DIN") (pintype "input"))
      (node (ref "R6") (pin "1") (pinfunction "1_1") (pintype "passive"))
    )
    (net (code "38") (name "Net-(Q1A-B)") (class "Default")
      (node (ref "Q1") (pin "5") (pinfunction "B_5") (pintype "passive"))
      (node (ref "R9") (pin "2") (pinfunction "2_2") (pintype "passive"))
    )
    (net (code "39") (name "Net-(Q1B-B)") (class "Default")
      (node (ref "Q1") (pin "2") (pinfunction "B_2") (pintype "passive"))
      (node (ref "R10") (pin "2") (pinfunction "2_2") (pintype "passive"))
    )
    (net (code "40") (name "Net-(U$1-2)") (class "Default")
      (node (ref "U$1") (pin "P$2") (pinfunction "2_P$2") (pintype "passive"))
      (node (ref "U$13") (pin "5") (pinfunction "L_5") (pintype "bidirectional"))
    )
    (net (code "41") (name "Net-(U$13-FB)") (class "Default")
      (node (ref "R20") (pin "2") (pinfunction "2_2") (pintype "passive"))
      (node (ref "R21") (pin "1") (pinfunction "1_1") (pintype "passive"))
      (node (ref "U$13") (pin "2") (pinfunction "FB_2") (pintype "bidirectional"))
    )
    (net (code "42") (name "Net-(U$15-FB)") (class "Default")
      (node (ref "C3") (pin "2") (pinfunction "2_2") (pintype "passive"))
      (node (ref "R39") (pin "1") (pinfunction "1_1") (pintype "passive"))
      (node (ref "R40") (pin "2") (pinfunction "2_2") (pintype "passive"))
      (node (ref "U$15") (pin "2") (pinfunction "FB_2") (pintype "bidirectional"))
    )
    (net (code "43") (name "Net-(U$15-NR{slash}SS)") (class "Default")
      (node (ref "C45") (pin "1") (pinfunction "1_1") (pintype "passive"))
      (node (ref "U$15") (pin "6") (pinfunction "NR/SS_6") (pintype "bidirectional"))
    )
    (net (code "44") (name "Net-(U1-USBDM)") (class "Default")
      (node (ref "R14") (pin "2") (pinfunction "2_2") (pintype "passive"))
      (node (ref "U1") (pin "12") (pinfunction "USBDM_12") (pintype "bidirectional"))
    )
    (net (code "45") (name "Net-(U1-USBDP)") (class "Default")
      (node (ref "R15") (pin "2") (pinfunction "2_2") (pintype "passive"))
      (node (ref "U1") (pin "11") (pinfunction "USBDP_11") (pintype "bidirectional"))
    )
    (net (code "46") (name "Net-(U3-PROG)") (class "Default")
      (node (ref "R17") (pin "2") (pinfunction "2_2") (pintype "passive"))
      (node (ref "U3") (pin "5") (pinfunction "PROG_5") (pintype "input"))
    )
    (net (code "47") (name "Net-(U3-STAT)") (class "Default")
      (node (ref "CHG2") (pin "C") (pinfunction "C_C") (pintype "passive"))
      (node (ref "U3") (pin "1") (pinfunction "STAT_1") (pintype "output"))
    )
    (net (code "48") (name "REFN0") (class "Default")
      (node (ref "SV2") (pin "5") (pinfunction "5_5") (pintype "passive"))
      (node (ref "U$9") (pin "8") (pinfunction "REFN0_8") (pintype "bidirectional"))
    )
    (net (code "49") (name "REFP0") (class "Default")
      (node (ref "SV2") (pin "6") (pinfunction "6_6") (pintype "passive"))
      (node (ref "U$9") (pin "9") (pinfunction "REFP0_9") (pintype "bidirectional"))
    )
    (net (code "50") (name "RTS") (class "Default")
      (node (ref "Q1") (pin "4") (pinfunction "E_4") (pintype "passive"))
      (node (ref "R10") (pin "1") (pinfunction "1_1") (pintype "passive"))
      (node (ref "U1") (pin "2") (pinfunction "~{RTS}_2") (pintype "bidirectional"))
    )
    (net (code "51") (name "RXD") (class "Default")
      (node (ref "R13") (pin "2") (pinfunction "2_2") (pintype "passive"))
      (node (ref "U1") (pin "4") (pinfunction "RXD_4") (pintype "bidirectional"))
    )
    (net (code "52") (name "SCL") (class "Default")
      (node (ref "IC1") (pin "42") (pinfunction "IO21_42") (pintype "power_in"))
      (node (ref "J4") (pin "4") (pinfunction "4_4") (pintype "passive"))
      (node (ref "R3") (pin "1") (pinfunction "1_1") (pintype "passive"))
    )
    (net (code "53") (name "SCL1") (class "Default")
      (node (ref "IC1") (pin "14") (pinfunction "IO25_14") (pintype "bidirectional"))
      (node (ref "J1") (pin "4") (pinfunction "4_4") (pintype "passive"))
      (node (ref "R18") (pin "1") (pinfunction "1_1") (pintype "passive"))
    )
    (net (code "54") (name "SCLK") (class "Default")
      (node (ref "IC1") (pin "35") (pinfunction "IO18_35") (pintype "bidirectional"))
      (node (ref "U$9") (pin "1") (pinfunction "SCLK_1") (pintype "bidirectional"))
    )
    (net (code "55") (name "SDA") (class "Default")
      (node (ref "IC1") (pin "16") (pinfunction "IO27_16") (pintype "bidirectional"))
      (node (ref "J4") (pin "3") (pinfunction "3_3") (pintype "passive"))
      (node (ref "R4") (pin "1") (pinfunction "1_1") (pintype "passive"))
    )
    (net (code "56") (name "SDA1") (class "Default")
      (node (ref "IC1") (pin "15") (pinfunction "IO26_15") (pintype "bidirectional"))
      (node (ref "J1") (pin "3") (pinfunction "3_3") (pintype "passive"))
      (node (ref "R5") (pin "1") (pinfunction "1_1") (pintype "passive"))
    )
    (net (code "57") (name "SENSOR_CAPN") (class "Default")
      (node (ref "IC1") (pin "7") (pinfunction "SENSOR_CAPN_7") (pintype "power_in"))
    )
    (net (code "58") (name "TXD") (class "Default")
      (node (ref "R12") (pin "2") (pinfunction "2_2") (pintype "passive"))
      (node (ref "U1") (pin "20") (pinfunction "TXD_20") (pintype "bidirectional"))
    )
    (net (code "59") (name "U0RXD") (class "Default")
      (node (ref "IC1") (pin "40") (pinfunction "U0RXD_40") (pintype "bidirectional"))
      (node (ref "R12") (pin "1") (pinfunction "1_1") (pintype "passive"))
    )
    (net (code "60") (name "U0TXD") (class "Default")
      (node (ref "IC1") (pin "41") (pinfunction "U0TXD_41") (pintype "bidirectional"))
      (node (ref "R13") (pin "1") (pinfunction "1_1") (pintype "passive"))
    )
    (net (code "61") (name "VBAT") (class "Default")
      (node (ref "C65") (pin "1") (pinfunction "1_1") (pintype "passive"))
      (node (ref "JP6") (pin "2") (pinfunction "2_2") (pintype "passive"))
      (node (ref "Q2") (pin "3") (pinfunction "D_3") (pintype "passive"))
      (node (ref "R25") (pin "2") (pinfunction "2_2") (pintype "passive"))
      (node (ref "U3") (pin "3") (pinfunction "VBAT_3") (pintype "power_in"))
    )
    (net (code "62") (name "VCC") (class "Default")
      (node (ref "C44") (pin "1") (pinfunction "1_1") (pintype "passive"))
      (node (ref "C83") (pin "1") (pinfunction "1_1") (pintype "passive"))
      (node (ref "R20") (pin "1") (pinfunction "1_1") (pintype "passive"))
      (node (ref "TP41") (pin "TP") (pinfunction "TP_TP") (pintype "input"))
      (node (ref "U$13") (pin "4") (pinfunction "VOUT_4") (pintype "bidirectional"))
      (node (ref "U$15") (pin "5") (pinfunction "EN_5") (pintype "bidirectional"))
      (node (ref "U$15") (pin "8") (pinfunction "IN_8") (pintype "bidirectional"))
    )
    (net (code "63") (name "VIN") (class "Default")
      (node (ref "C1") (pin "1") (pinfunction "1_1") (pintype "passive"))
      (node (ref "C63") (pin "1") (pinfunction "1_1") (pintype "passive"))
      (node (ref "C72") (pin "2") (pinfunction "2_2") (pintype "passive"))
      (node (ref "D1") (pin "C") (pinfunction "C_C") (pintype "passive"))
      (node (ref "Q2") (pin "2") (pinfunction "S_2") (pintype "passive"))
      (node (ref "S2") (pin "3") (pinfunction "S_3") (pintype "passive"))
      (node (ref "U$1") (pin "P$1") (pinfunction "1_P$1") (pintype "passive"))
      (node (ref "U$13") (pin "1") (pinfunction "VIN_1") (pintype "bidirectional"))
      (node (ref "U8") (pin "1") (pinfunction "IN_1") (pintype "input"))
    )
    (net (code "64") (name "VUSB") (class "Default")
      (node (ref "C60") (pin "1") (pinfunction "1_1") (pintype "passive"))
      (node (ref "C61") (pin "1") (pinfunction "1_1") (pintype "passive"))
      (node (ref "C64") (pin "1") (pinfunction "1_1") (pintype "passive"))
      (node (ref "D1") (pin "A") (pinfunction "A_A") (pintype "passive"))
      (node (ref "JP7") (pin "1") (pinfunction "VCC_1") (pintype "bidirectional"))
      (node (ref "Q2") (pin "1") (pinfunction "G_1") (pintype "passive"))
      (node (ref "R16") (pin "1") (pinfunction "1_1") (pintype "passive"))
      (node (ref "R23") (pin "2") (pinfunction "2_2") (pintype "passive"))
      (node (ref "U1") (pin "15") (pinfunction "VCC_15") (pintype "bidirectional"))
      (node (ref "U3") (pin "4") (pinfunction "VIN_4") (pintype "power_in"))
    )
    (net (code "65") (name "WS2812") (class "Default")
      (node (ref "IC1") (pin "17") (pinfunction "IO14_17") (pintype "bidirectional"))
      (node (ref "R6") (pin "2") (pinfunction "2_2") (pintype "passive"))
    )
    (net (code "66") (name "unconnected-(IC1A-CAP1_NC-Pad48)") (class "Default")
      (node (ref "IC1") (pin "48") (pinfunction "CAP1_NC_48") (pintype "bidirectional"))
    )
    (net (code "67") (name "unconnected-(IC1A-CAP2_NC-Pad47)") (class "Default")
      (node (ref "IC1") (pin "47") (pinfunction "CAP2_NC_47") (pintype "bidirectional"))
    )
    (net (code "68") (name "unconnected-(IC1A-IO2-Pad22)") (class "Default")
      (node (ref "IC1") (pin "22") (pinfunction "IO2_22") (pintype "bidirectional"))
    )
    (net (code "69") (name "unconnected-(IC1A-IO5-Pad34)") (class "Default")
      (node (ref "IC1") (pin "34") (pinfunction "IO5_34") (pintype "bidirectional"))
    )
    (net (code "70") (name "unconnected-(IC1A-IO13-Pad20)") (class "Default")
      (node (ref "IC1") (pin "20") (pinfunction "IO13_20") (pintype "bidirectional"))
    )
    (net (code "71") (name "unconnected-(IC1A-SD0-Pad32)") (class "Default")
      (node (ref "IC1") (pin "32") (pinfunction "SD0_32") (pintype "bidirectional"))
    )
    (net (code "72") (name "unconnected-(IC1A-SD1-Pad33)") (class "Default")
      (node (ref "IC1") (pin "33") (pinfunction "SD1_33") (pintype "bidirectional"))
    )
    (net (code "73") (name "unconnected-(IC1A-SENSOR_CAPP-Pad6)") (class "Default")
      (node (ref "IC1") (pin "6") (pinfunction "SENSOR_CAPP_6") (pintype "bidirectional"))
    )
    (net (code "74") (name "unconnected-(IC1A-XTAL_N_NC-Pad44)") (class "Default")
      (node (ref "IC1") (pin "44") (pinfunction "XTAL_N_NC_44") (pintype "bidirectional"))
    )
    (net (code "75") (name "unconnected-(IC1A-XTAL_P_NC-Pad45)") (class "Default")
      (node (ref "IC1") (pin "45") (pinfunction "XTAL_P_NC_45") (pintype "bidirectional"))
    )
    (net (code "76") (name "unconnected-(JP7-ID-Pad4)") (class "Default")
      (node (ref "JP7") (pin "4") (pinfunction "ID_4") (pintype "bidirectional"))
    )
    (net (code "77") (name "unconnected-(LED1-DO-Pad2-DOUT)") (class "Default")
      (node (ref "LED1") (pin "2-DOUT") (pinfunction "DO_2-DOUT") (pintype "output"))
    )
    (net (code "78") (name "unconnected-(SW2-P1-PadA')") (class "Default")
      (node (ref "SW2") (pin "A'") (pinfunction "P1_A'") (pintype "passive"))
    )
    (net (code "79") (name "unconnected-(TP5-PadTP)") (class "Default")
      (node (ref "TP5") (pin "TP") (pinfunction "TP_TP") (pintype "input"))
    )
    (net (code "80") (name "unconnected-(TP6-PadTP)") (class "Default")
      (node (ref "TP6") (pin "TP") (pinfunction "TP_TP") (pintype "input"))
    )
    (net (code "81") (name "unconnected-(TP7-PadTP)") (class "Default")
      (node (ref "TP7") (pin "TP") (pinfunction "TP_TP") (pintype "input"))
    )
    (net (code "82") (name "unconnected-(TP8-PadTP)") (class "Default")
      (node (ref "TP8") (pin "TP") (pinfunction "TP_TP") (pintype "input"))
    )
    (net (code "83") (name "unconnected-(TP9-PadTP)") (class "Default")
      (node (ref "TP9") (pin "TP") (pinfunction "TP_TP") (pintype "input"))
    )
    (net (code "84") (name "unconnected-(TP11-PadTP)") (class "Default")
      (node (ref "TP11") (pin "TP") (pinfunction "TP_TP") (pintype "input"))
    )
    (net (code "85") (name "unconnected-(TP12-PadTP)") (class "Default")
      (node (ref "TP12") (pin "TP") (pinfunction "TP_TP") (pintype "input"))
    )
    (net (code "86") (name "unconnected-(TP13-PadTP)") (class "Default")
      (node (ref "TP13") (pin "TP") (pinfunction "TP_TP") (pintype "input"))
    )
    (net (code "87") (name "unconnected-(TP14-PadTP)") (class "Default")
      (node (ref "TP14") (pin "TP") (pinfunction "TP_TP") (pintype "input"))
    )
    (net (code "88") (name "unconnected-(TP15-PadTP)") (class "Default")
      (node (ref "TP15") (pin "TP") (pinfunction "TP_TP") (pintype "input"))
    )
    (net (code "89") (name "unconnected-(TP16-PadTP)") (class "Default")
      (node (ref "TP16") (pin "TP") (pinfunction "TP_TP") (pintype "input"))
    )
    (net (code "90") (name "unconnected-(TP17-PadTP)") (class "Default")
      (node (ref "TP17") (pin "TP") (pinfunction "TP_TP") (pintype "input"))
    )
    (net (code "91") (name "unconnected-(TP18-PadTP)") (class "Default")
      (node (ref "TP18") (pin "TP") (pinfunction "TP_TP") (pintype "input"))
    )
    (net (code "92") (name "unconnected-(TP19-PadTP)") (class "Default")
      (node (ref "TP19") (pin "TP") (pinfunction "TP_TP") (pintype "input"))
    )
    (net (code "93") (name "unconnected-(TP20-PadTP)") (class "Default")
      (node (ref "TP20") (pin "TP") (pinfunction "TP_TP") (pintype "input"))
    )
    (net (code "94") (name "unconnected-(TP21-PadTP)") (class "Default")
      (node (ref "TP21") (pin "TP") (pinfunction "TP_TP") (pintype "input"))
    )
    (net (code "95") (name "unconnected-(TP22-PadTP)") (class "Default")
      (node (ref "TP22") (pin "TP") (pinfunction "TP_TP") (pintype "input"))
    )
    (net (code "96") (name "unconnected-(TP23-PadTP)") (class "Default")
      (node (ref "TP23") (pin "TP") (pinfunction "TP_TP") (pintype "input"))
    )
    (net (code "97") (name "unconnected-(TP24-PadTP)") (class "Default")
      (node (ref "TP24") (pin "TP") (pinfunction "TP_TP") (pintype "input"))
    )
    (net (code "98") (name "unconnected-(TP25-PadTP)") (class "Default")
      (node (ref "TP25") (pin "TP") (pinfunction "TP_TP") (pintype "input"))
    )
    (net (code "99") (name "unconnected-(TP26-PadTP)") (class "Default")
      (node (ref "TP26") (pin "TP") (pinfunction "TP_TP") (pintype "input"))
    )
    (net (code "100") (name "unconnected-(TP27-PadTP)") (class "Default")
      (node (ref "TP27") (pin "TP") (pinfunction "TP_TP") (pintype "input"))
    )
    (net (code "101") (name "unconnected-(TP28-PadTP)") (class "Default")
      (node (ref "TP28") (pin "TP") (pinfunction "TP_TP") (pintype "input"))
    )
    (net (code "102") (name "unconnected-(TP29-PadTP)") (class "Default")
      (node (ref "TP29") (pin "TP") (pinfunction "TP_TP") (pintype "input"))
    )
    (net (code "103") (name "unconnected-(TP30-PadTP)") (class "Default")
      (node (ref "TP30") (pin "TP") (pinfunction "TP_TP") (pintype "input"))
    )
    (net (code "104") (name "unconnected-(TP31-PadTP)") (class "Default")
      (node (ref "TP31") (pin "TP") (pinfunction "TP_TP") (pintype "input"))
    )
    (net (code "105") (name "unconnected-(TP32-PadTP)") (class "Default")
      (node (ref "TP32") (pin "TP") (pinfunction "TP_TP") (pintype "input"))
    )
    (net (code "106") (name "unconnected-(TP33-PadTP)") (class "Default")
      (node (ref "TP33") (pin "TP") (pinfunction "TP_TP") (pintype "input"))
    )
    (net (code "107") (name "unconnected-(TP34-PadTP)") (class "Default")
      (node (ref "TP34") (pin "TP") (pinfunction "TP_TP") (pintype "input"))
    )
    (net (code "108") (name "unconnected-(TP36-PadTP)") (class "Default")
      (node (ref "TP36") (pin "TP") (pinfunction "TP_TP") (pintype "input"))
    )
    (net (code "109") (name "unconnected-(TP37-PadTP)") (class "Default")
      (node (ref "TP37") (pin "TP") (pinfunction "TP_TP") (pintype "input"))
    )
    (net (code "110") (name "unconnected-(TP38-PadTP)") (class "Default")
      (node (ref "TP38") (pin "TP") (pinfunction "TP_TP") (pintype "input"))
    )
    (net (code "111") (name "unconnected-(TP39-PadTP)") (class "Default")
      (node (ref "TP39") (pin "TP") (pinfunction "TP_TP") (pintype "input"))
    )
    (net (code "112") (name "unconnected-(TP40-PadTP)") (class "Default")
      (node (ref "TP40") (pin "TP") (pinfunction "TP_TP") (pintype "input"))
    )
    (net (code "113") (name "unconnected-(TP42-PadTP)") (class "Default")
      (node (ref "TP42") (pin "TP") (pinfunction "TP_TP") (pintype "input"))
    )
    (net (code "114") (name "unconnected-(TP44-PadTP)") (class "Default")
      (node (ref "TP44") (pin "TP") (pinfunction "TP_TP") (pintype "input"))
    )
    (net (code "115") (name "unconnected-(TP45-PadTP)") (class "Default")
      (node (ref "TP45") (pin "TP") (pinfunction "TP_TP") (pintype "input"))
    )
    (net (code "116") (name "unconnected-(TP46-PadTP)") (class "Default")
      (node (ref "TP46") (pin "TP") (pinfunction "TP_TP") (pintype "input"))
    )
    (net (code "117") (name "unconnected-(TP48-PadTP)") (class "Default")
      (node (ref "TP48") (pin "TP") (pinfunction "TP_TP") (pintype "input"))
    )
    (net (code "118") (name "unconnected-(TP50-PadTP)") (class "Default")
      (node (ref "TP50") (pin "TP") (pinfunction "TP_TP") (pintype "input"))
    )
    (net (code "119") (name "unconnected-(TP51-PadTP)") (class "Default")
      (node (ref "TP51") (pin "TP") (pinfunction "TP_TP") (pintype "input"))
    )
    (net (code "120") (name "unconnected-(TP52-PadTP)") (class "Default")
      (node (ref "TP52") (pin "TP") (pinfunction "TP_TP") (pintype "input"))
    )
    (net (code "121") (name "unconnected-(TP53-PadTP)") (class "Default")
      (node (ref "TP53") (pin "TP") (pinfunction "TP_TP") (pintype "input"))
    )
    (net (code "122") (name "unconnected-(TP54-PadTP)") (class "Default")
      (node (ref "TP54") (pin "TP") (pinfunction "TP_TP") (pintype "input"))
    )
    (net (code "123") (name "unconnected-(TP55-PadTP)") (class "Default")
      (node (ref "TP55") (pin "TP") (pinfunction "TP_TP") (pintype "input"))
    )
    (net (code "124") (name "unconnected-(TP56-PadTP)") (class "Default")
      (node (ref "TP56") (pin "TP") (pinfunction "TP_TP") (pintype "input"))
    )
    (net (code "125") (name "unconnected-(TP58-PadTP)") (class "Default")
      (node (ref "TP58") (pin "TP") (pinfunction "TP_TP") (pintype "input"))
    )
    (net (code "126") (name "unconnected-(TP59-PadTP)") (class "Default")
      (node (ref "TP59") (pin "TP") (pinfunction "TP_TP") (pintype "input"))
    )
    (net (code "127") (name "unconnected-(TP60-PadTP)") (class "Default")
      (node (ref "TP60") (pin "TP") (pinfunction "TP_TP") (pintype "input"))
    )
    (net (code "128") (name "unconnected-(TP62-PadTP)") (class "Default")
      (node (ref "TP62") (pin "TP") (pinfunction "TP_TP") (pintype "input"))
    )
    (net (code "129") (name "unconnected-(TP63-PadTP)") (class "Default")
      (node (ref "TP63") (pin "TP") (pinfunction "TP_TP") (pintype "input"))
    )
    (net (code "130") (name "unconnected-(TP65-PadTP)") (class "Default")
      (node (ref "TP65") (pin "TP") (pinfunction "TP_TP") (pintype "input"))
    )
    (net (code "131") (name "unconnected-(TP66-PadTP)") (class "Default")
      (node (ref "TP66") (pin "TP") (pinfunction "TP_TP") (pintype "input"))
    )
    (net (code "132") (name "unconnected-(TP68-PadTP)") (class "Default")
      (node (ref "TP68") (pin "TP") (pinfunction "TP_TP") (pintype "input"))
    )
    (net (code "133") (name "unconnected-(TP69-PadTP)") (class "Default")
      (node (ref "TP69") (pin "TP") (pinfunction "TP_TP") (pintype "input"))
    )
    (net (code "134") (name "unconnected-(TP70-PadTP)") (class "Default")
      (node (ref "TP70") (pin "TP") (pinfunction "TP_TP") (pintype "input"))
    )
    (net (code "135") (name "unconnected-(TP71-PadTP)") (class "Default")
      (node (ref "TP71") (pin "TP") (pinfunction "TP_TP") (pintype "input"))
    )
    (net (code "136") (name "unconnected-(TP72-PadTP)") (class "Default")
      (node (ref "TP72") (pin "TP") (pinfunction "TP_TP") (pintype "input"))
    )
    (net (code "137") (name "unconnected-(TP73-PadTP)") (class "Default")
      (node (ref "TP73") (pin "TP") (pinfunction "TP_TP") (pintype "input"))
    )
    (net (code "138") (name "unconnected-(TP74-PadTP)") (class "Default")
      (node (ref "TP74") (pin "TP") (pinfunction "TP_TP") (pintype "input"))
    )
    (net (code "139") (name "unconnected-(U1-CBUS0-Pad18)") (class "Default")
      (node (ref "U1") (pin "18") (pinfunction "CBUS0_18") (pintype "bidirectional"))
    )
    (net (code "140") (name "unconnected-(U1-CBUS1-Pad17)") (class "Default")
      (node (ref "U1") (pin "17") (pinfunction "CBUS1_17") (pintype "bidirectional"))
    )
    (net (code "141") (name "unconnected-(U1-CBUS2-Pad10)") (class "Default")
      (node (ref "U1") (pin "10") (pinfunction "CBUS2_10") (pintype "bidirectional"))
    )
    (net (code "142") (name "unconnected-(U1-CBUS3-Pad19)") (class "Default")
      (node (ref "U1") (pin "19") (pinfunction "CBUS3_19") (pintype "bidirectional"))
    )
    (net (code "143") (name "unconnected-(U1-~{CTS}-Pad9)") (class "Default")
      (node (ref "U1") (pin "9") (pinfunction "~{CTS}_9") (pintype "bidirectional"))
    )
    (net (code "144") (name "unconnected-(U1-~{DCD}-Pad8)") (class "Default")
      (node (ref "U1") (pin "8") (pinfunction "~{DCD}_8") (pintype "bidirectional"))
    )
    (net (code "145") (name "unconnected-(U1-~{DSR}-Pad7)") (class "Default")
      (node (ref "U1") (pin "7") (pinfunction "~{DSR}_7") (pintype "bidirectional"))
    )
    (net (code "146") (name "unconnected-(U1-~{RI}-Pad5)") (class "Default")
      (node (ref "U1") (pin "5") (pinfunction "~{RI}_5") (pintype "bidirectional"))
    )
    (net (code "147") (name "unconnected-(U8-BP-Pad4)") (class "Default")
      (node (ref "U8") (pin "4") (pinfunction "BP_4") (pintype "input"))
    )
    (net (code "148") (name "~{CS1}") (class "Default")
      (node (ref "IC1") (pin "38") (pinfunction "IO19_38") (pintype "bidirectional"))
      (node (ref "U$9") (pin "2") (pinfunction "~{CS}_2") (pintype "bidirectional"))
    )
    (net (code "149") (name "~{DRDY}") (class "Default")
      (node (ref "IC1") (pin "10") (pinfunction "IO34_10") (pintype "bidirectional"))
      (node (ref "U$9") (pin "14") (pinfunction "~{DRDY}_14") (pintype "bidirectional"))
    )
  )
)
